# LED.net
KiCad netlist of a schematic drawn in EasyEDA Pro
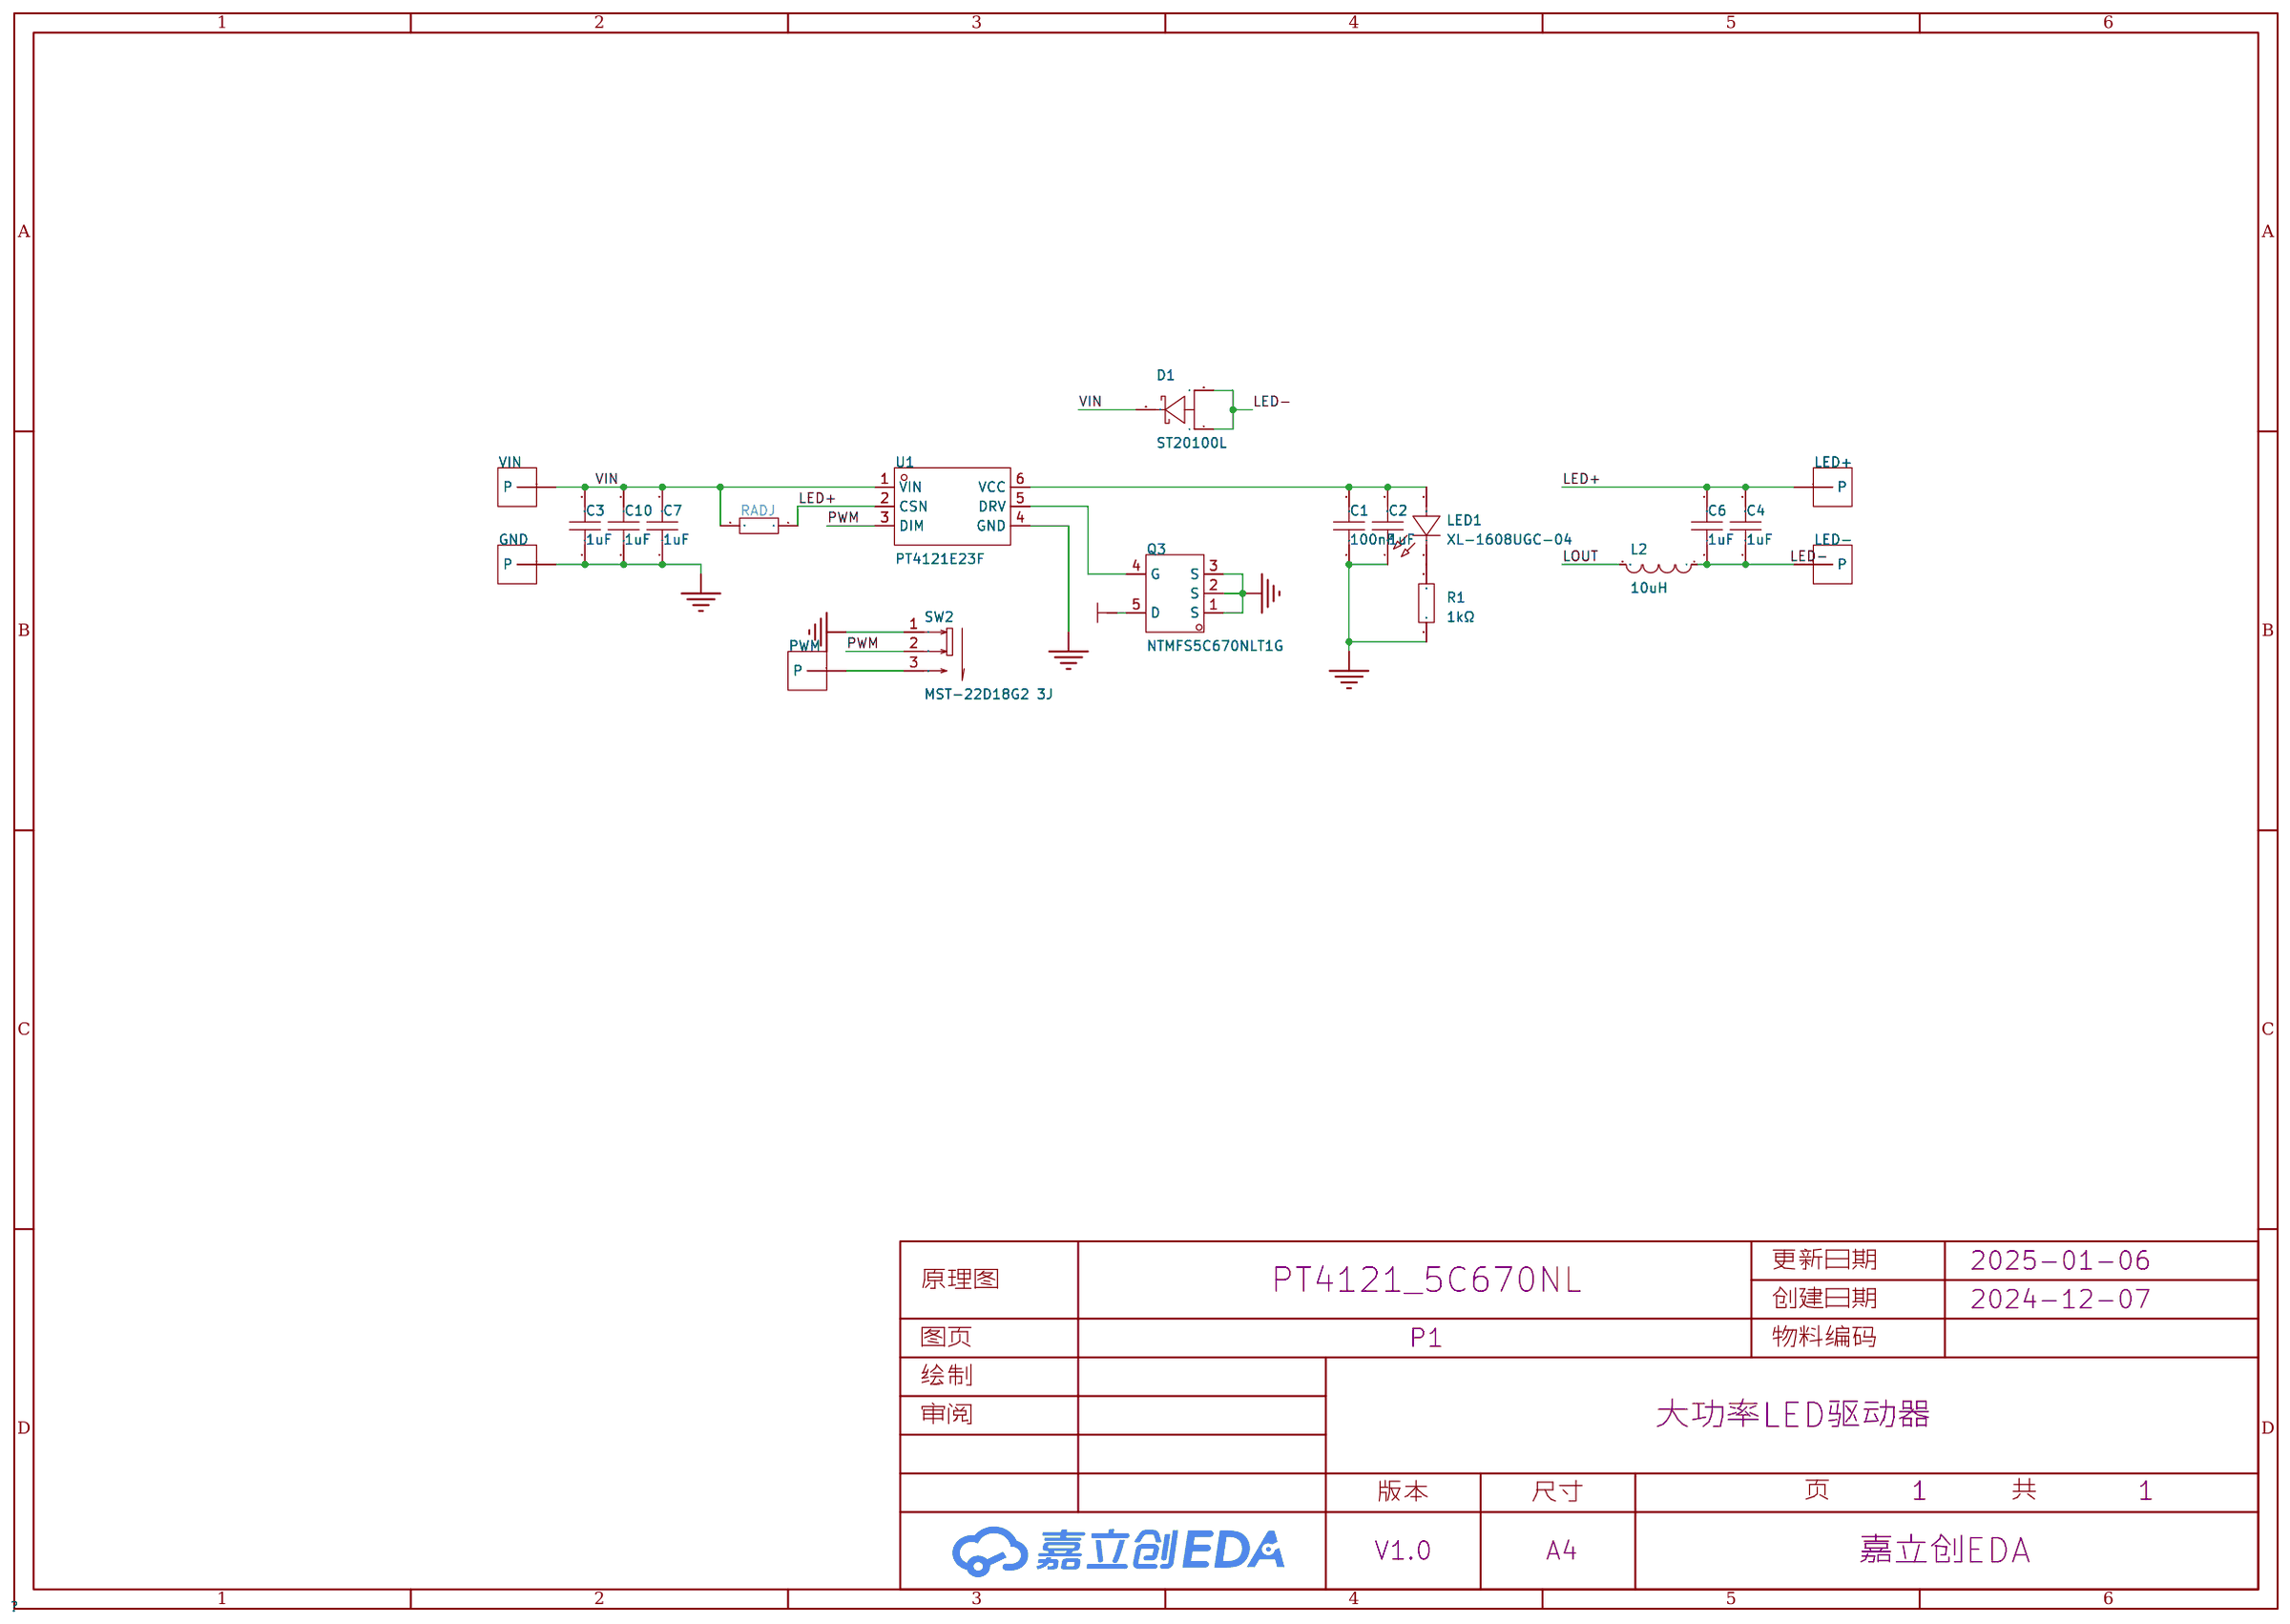
[diagram p0: schematic sheet]

(export (version "E")
  (design (tool "Eeschema 10.0.6"))
  (components
    (comp (ref "C1")
      (value "100nF")
      (footprint "easyedapro:C0603")
      (libsource (lib "easyedapro") (part "CapAcitance"))
    )
    (comp (ref "C2")
      (value "1uF")
      (footprint "easyedapro:C0603")
      (libsource (lib "easyedapro") (part "CapAcitance"))
    )
    (comp (ref "C3")
      (value "1uF")
      (footprint "easyedapro:C0603")
      (fields
        (field (name "Manufacturer Part") "CL21B105KBFNNNE")
        (field (name "Manufacturer") "SAMSUNG(三星)")
      )
      (libsource (lib "easyedapro") (part "CapAcitance"))
    )
    (comp (ref "C4")
      (value "1uF")
      (footprint "easyedapro:C0603")
      (fields
        (field (name "Manufacturer Part") "CL21B105KBFNNNE")
        (field (name "Manufacturer") "SAMSUNG(三星)")
      )
      (libsource (lib "easyedapro") (part "CapAcitance"))
    )
    (comp (ref "C6")
      (value "1uF")
      (footprint "easyedapro:C0603")
      (fields
        (field (name "Manufacturer Part") "CL21B105KBFNNNE")
        (field (name "Manufacturer") "SAMSUNG(三星)")
      )
      (libsource (lib "easyedapro") (part "CapAcitance"))
    )
    (comp (ref "C7")
      (value "1uF")
      (footprint "easyedapro:C0603")
      (fields
        (field (name "Manufacturer Part") "CL21B105KBFNNNE")
        (field (name "Manufacturer") "SAMSUNG(三星)")
      )
      (libsource (lib "easyedapro") (part "CapAcitance"))
    )
    (comp (ref "C10")
      (value "1uF")
      (footprint "easyedapro:C0603")
      (fields
        (field (name "Manufacturer Part") "CL21B105KBFNNNE")
        (field (name "Manufacturer") "SAMSUNG(三星)")
      )
      (libsource (lib "easyedapro") (part "CapAcitance"))
    )
    (comp (ref "D1")
      (value "ST20100L")
      (footprint "easyedapro:TO-277_3P-L5.7-W4.2-LS6.5-BR")
      (description "二极管配置:独立式;正向压降(Vf):650mV@20A;直流反向耐压(Vr):100V;整流电流:20A;")
      (fields (field (name "Manufacturer") "CJ(江苏长电/长晶)"))
      (libsource (lib "easyedapro") (part "ST20100L"))
    )
    (comp (ref "GND")
      (value "~")
      (footprint "easyedapro:焊盘1.6*2.2mm")
      (description "焊盘：1.6mm*2.2mm")
      (libsource (lib "easyedapro") (part "焊盘1.6x2.2"))
    )
    (comp (ref "L2")
      (value "10uH")
      (footprint "easyedapro:IND-TH_L23.0-W12.0-P9.00-D1.3")
      (description "电感值:10uH;精度:±20%;额定电流:18A;类型:磁环电感;")
      (fields
        (field (name "Manufacturer Part") "PDMTAT068125-100MLU")
        (field (name "Manufacturer") "PROD(谱罗德)")
      )
      (libsource (lib "easyedapro") (part "PDMTAT068125-100MLU"))
    )
    (comp (ref "LED+")
      (value "~")
      (footprint "easyedapro:焊盘1.6*2.2mm")
      (description "焊盘：1.6mm*2.2mm")
      (libsource (lib "easyedapro") (part "焊盘1.6x2.2"))
    )
    (comp (ref "LED-")
      (value "~")
      (footprint "easyedapro:焊盘1.6*2.2mm")
      (description "焊盘：1.6mm*2.2mm")
      (libsource (lib "easyedapro") (part "焊盘1.6x2.2"))
    )
    (comp (ref "LED1")
      (value "XL-1608UGC-04")
      (footprint "easyedapro:LED0603-RD_GREEN")
      (fields (field (name "Manufacturer") "XINGLIGHT(成兴光)"))
      (libsource (lib "easyedapro") (part "XL-1608UGC-04"))
    )
    (comp (ref "PWM")
      (value "~")
      (footprint "easyedapro:焊盘1.6*2.2mm")
      (description "焊盘：1.6mm*2.2mm")
      (libsource (lib "easyedapro") (part "焊盘1.6x2.2"))
    )
    (comp (ref "Q3")
      (value "NTMFS5C670NLT1G")
      (footprint "easyedapro:DFN-5_L6.1-W5.1-P1.27-BL")
      (fields (field (name "Manufacturer") "onsemi(安森美)"))
      (libsource (lib "easyedapro") (part "NTMFS5C670NLT1G"))
    )
    (comp (ref "R1")
      (value "1kΩ")
      (footprint "easyedapro:R0603")
      (description "电阻类型:厚膜电阻;阻值:1kΩ;精度:±1%;功率:100mW;最大工作电压:75V;温度系数:±100ppm/°C;")
      (fields (field (name "Manufacturer Part") "RC0603FR-071KL") (field (name "Manufacturer") "YAGEO(国巨)"))
      (libsource (lib "easyedapro") (part "RC0603FR-071KL"))
    )
    (comp (ref "RADJ")
      (value "ADJMR")
      (footprint "easyedapro:R0603")
      (fields (field (name "Manufacturer Part") "EBWM2512F1L00S9") (field (name "Manufacturer") "RESI(开步睿思)"))
      (libsource (lib "easyedapro") (part "电阻"))
    )
    (comp (ref "SW2")
      (value "MST-22D18G2 3J")
      (footprint "easyedapro:SW-SMD_SHOUHAN_MST-22D18G23J_C2875122")
      (description "电路结构:单刀双掷;安装方式:立贴;开关颜色:-;额定电流(DC):50mA;额定电压(DC):12V;额定电流(AC):-;额定电压(AC):-;机械寿命:1万次;")
      (fields (field (name "Manufacturer") "SHOU HAN(首韩)"))
      (libsource (lib "easyedapro") (part "MST-22D18G2 3J_C2875122"))
    )
    (comp (ref "U1")
      (value "PT4121E23F")
      (footprint "easyedapro:SOT-23-6_L2.9-W1.6-P0.95-LS2.8-BR")
      (fields (field (name "Manufacturer") "PowTech(华润矽威)"))
      (libsource (lib "easyedapro") (part "PT4121E23F"))
    )
    (comp (ref "VIN")
      (value "~")
      (footprint "easyedapro:焊盘1.6*2.2mm")
      (description "焊盘：1.6mm*2.2mm")
      (libsource (lib "easyedapro") (part "焊盘1.6x2.2"))
    )
  )
  (nets
    (net (code "1") (name "/LED+") (class "Default")
      (node (ref "C4") (pin "2") (pinfunction "2_2") (pintype "input"))
      (node (ref "C6") (pin "2") (pinfunction "2_2") (pintype "input"))
      (node (ref "LED+") (pin "1") (pinfunction "P_1") (pintype "input"))
      (node (ref "RADJ") (pin "1") (pinfunction "1_1") (pintype "input"))
      (node (ref "U1") (pin "2") (pinfunction "CSN_2") (pintype "input"))
    )
    (net (code "2") (name "/LED-") (class "Default")
      (node (ref "C4") (pin "1") (pinfunction "1_1") (pintype "input"))
      (node (ref "C6") (pin "1") (pinfunction "1_1") (pintype "input"))
      (node (ref "D1") (pin "1") (pinfunction "A_1") (pintype "unspecified"))
      (node (ref "D1") (pin "3") (pinfunction "A_3") (pintype "unspecified"))
      (node (ref "L2") (pin "1") (pinfunction "1_1") (pintype "unspecified"))
      (node (ref "LED-") (pin "1") (pinfunction "P_1") (pintype "input"))
    )
    (net (code "3") (name "/PWM") (class "Default")
      (node (ref "SW2") (pin "2") (pinfunction "2_2") (pintype "unspecified"))
      (node (ref "U1") (pin "3") (pinfunction "DIM_3") (pintype "input"))
    )
    (net (code "4") (name "/VIN") (class "Default")
      (node (ref "C10") (pin "2") (pinfunction "2_2") (pintype "input"))
      (node (ref "C3") (pin "2") (pinfunction "2_2") (pintype "input"))
      (node (ref "C7") (pin "2") (pinfunction "2_2") (pintype "input"))
      (node (ref "D1") (pin "2") (pinfunction "K_2") (pintype "unspecified"))
      (node (ref "RADJ") (pin "2") (pinfunction "2_2") (pintype "input"))
      (node (ref "U1") (pin "1") (pinfunction "VIN_1") (pintype "input"))
      (node (ref "VIN") (pin "1") (pinfunction "P_1") (pintype "input"))
    )
    (net (code "5") (name "GND") (class "Default")
      (node (ref "C1") (pin "1") (pinfunction "1_1") (pintype "input"))
      (node (ref "C10") (pin "1") (pinfunction "1_1") (pintype "input"))
      (node (ref "C2") (pin "1") (pinfunction "1_1") (pintype "input"))
      (node (ref "C3") (pin "1") (pinfunction "1_1") (pintype "input"))
      (node (ref "C7") (pin "1") (pinfunction "1_1") (pintype "input"))
      (node (ref "GND") (pin "1") (pinfunction "P_1") (pintype "input"))
      (node (ref "Q3") (pin "1") (pinfunction "S_1") (pintype "unspecified"))
      (node (ref "Q3") (pin "2") (pinfunction "S_2") (pintype "unspecified"))
      (node (ref "Q3") (pin "3") (pinfunction "S_3") (pintype "unspecified"))
      (node (ref "R1") (pin "1") (pinfunction "1_1") (pintype "input"))
      (node (ref "SW2") (pin "1") (pinfunction "1_1") (pintype "unspecified"))
      (node (ref "U1") (pin "4") (pinfunction "GND_4") (pintype "input"))
    )
    (net (code "6") (name "LOUT") (class "Default")
      (node (ref "L2") (pin "2") (pinfunction "2_2") (pintype "unspecified"))
      (node (ref "Q3") (pin "5") (pinfunction "D_5") (pintype "unspecified"))
    )
    (net (code "7") (name "Net-(LED1-A)") (class "Default")
      (node (ref "C1") (pin "2") (pinfunction "2_2") (pintype "input"))
      (node (ref "C2") (pin "2") (pinfunction "2_2") (pintype "input"))
      (node (ref "LED1") (pin "2") (pinfunction "A_2") (pintype "unspecified"))
      (node (ref "U1") (pin "6") (pinfunction "VCC_6") (pintype "input"))
    )
    (net (code "8") (name "Net-(LED1-K)") (class "Default")
      (node (ref "LED1") (pin "1") (pinfunction "K_1") (pintype "unspecified"))
      (node (ref "R1") (pin "2") (pinfunction "2_2") (pintype "input"))
    )
    (net (code "9") (name "Net-(PWM-P)") (class "Default")
      (node (ref "PWM") (pin "1") (pinfunction "P_1") (pintype "input"))
      (node (ref "SW2") (pin "3") (pinfunction "3_3") (pintype "unspecified"))
    )
    (net (code "10") (name "Net-(Q3-G)") (class "Default")
      (node (ref "Q3") (pin "4") (pinfunction "G_4") (pintype "unspecified"))
      (node (ref "U1") (pin "5") (pinfunction "DRV_5") (pintype "input"))
    )
  )
)
